# ProProject___2023-11-25.net
KiCad netlist of a schematic drawn in EasyEDA Pro
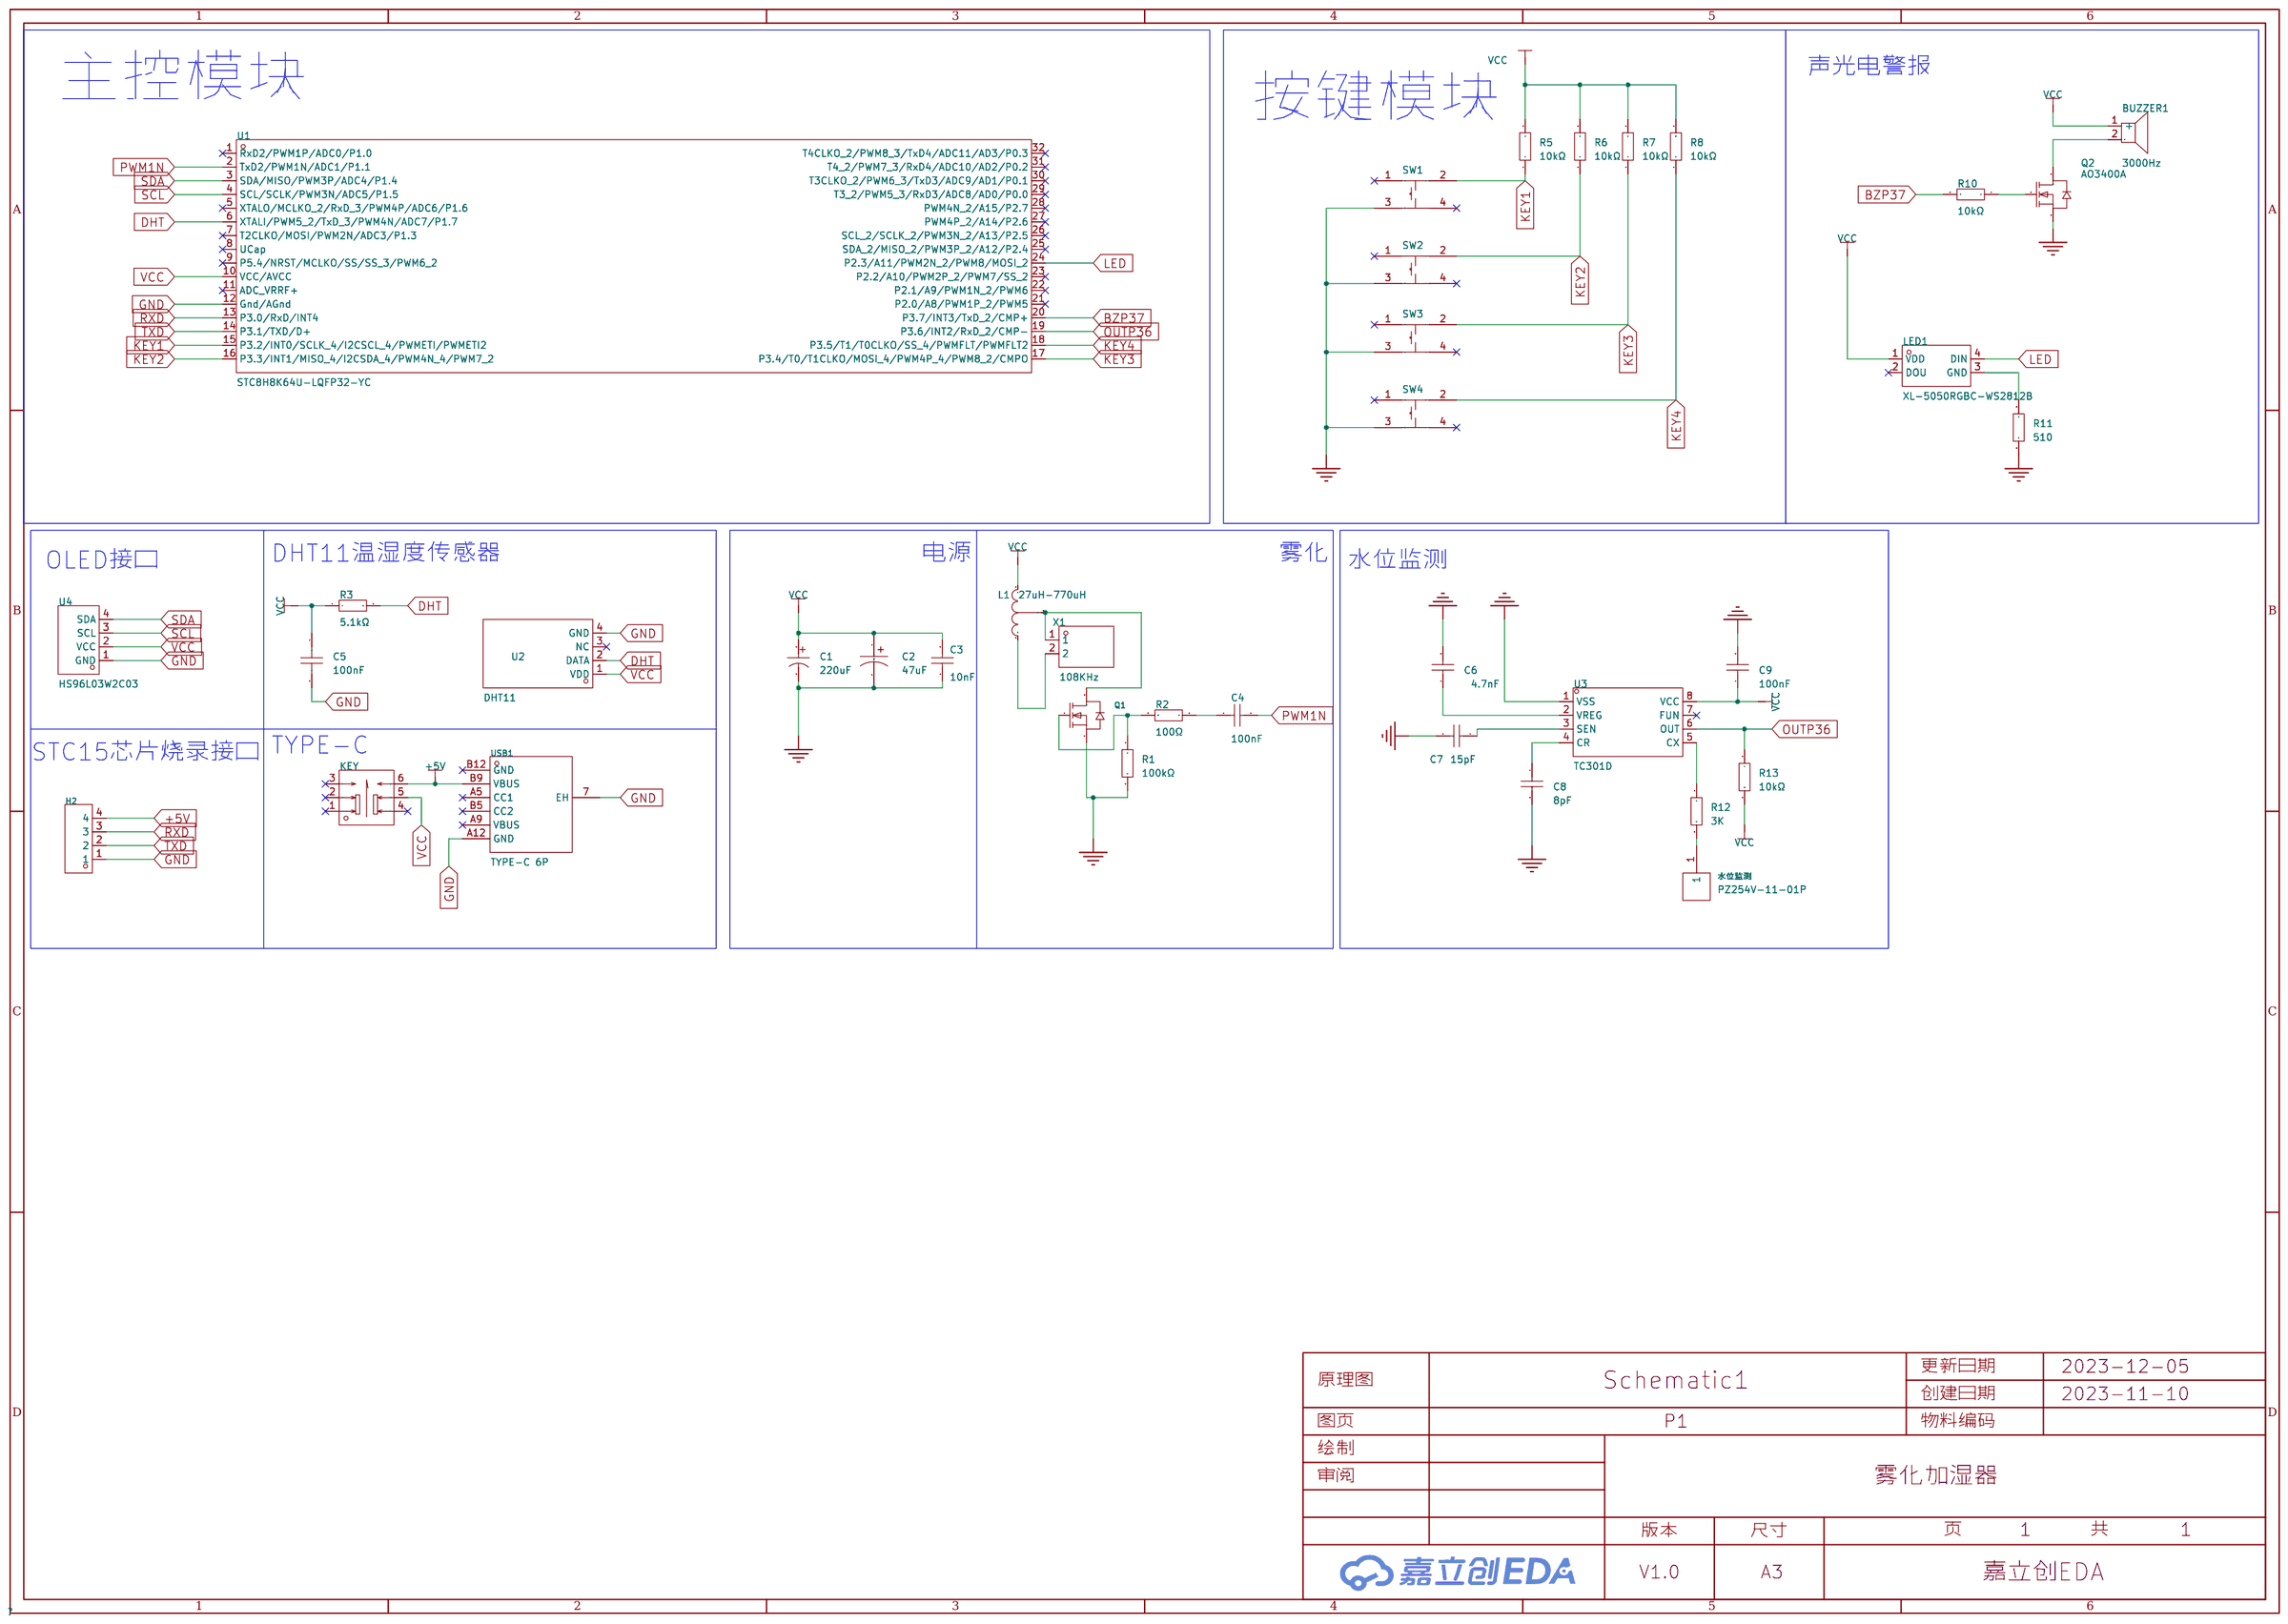
[diagram p0: schematic sheet]

(export (version "E")
  (design (tool "Eeschema 10.0.6"))
  (components
    (comp (ref "BUZZER1")
      (value "3000Hz")
      (footprint "easyedapro:BUZ-TH_BD9.6-P5.00-D0.7-FD")
      (description "驱动方式:有源(内含驱动线路);构造类型:电磁式;额定电压:5V;工作电压:4V~8V;频率:3000Hz;声压(SPL):85dB@5V,10cm;直径(φD):9mm;高度:5.7mm;")
      (fields (field (name "Manufacturer Part") "HNB09A05") (field (name "Manufacturer") "华能"))
      (libsource (lib "easyedapro") (part "HNB09A05"))
    )
    (comp (ref "C1")
      (value "220uF")
      (footprint "easyedapro:CAP-TH_BD10.0-P5.00-D1.0-FD")
      (description "容值:220uF;精度:±20%;额定电压:25V;纹波电流:-;等效串联电阻:-;")
      (fields (field (name "Manufacturer Part") "RNG221M1EBK-1012") (field (name "Manufacturer") "lelon(立隆)"))
      (libsource (lib "easyedapro") (part "RNG221M1EBK-1012"))
    )
    (comp (ref "C2")
      (value "47uF")
      (footprint "easyedapro:CAP-TH_BD5.0-P2.00-D0.8-FD")
      (description "容值:47uF;精度:±20%;额定电压:16V;纹波电流:95mA@100kHz;等效串联电阻:2.5Ω@100kHz;")
      (fields
        (field (name "Manufacturer Part") "01EC1882SHG47uF16V")
        (field (name "Manufacturer") "KNSCHA(科尼盛)")
      )
      (libsource (lib "easyedapro") (part "01EC1882SHG47UF16V"))
    )
    (comp (ref "C3")
      (value "10nF")
      (footprint "easyedapro:C0805")
      (description "容值:10nF;精度:±10%;额定电压:50V;材质(温度系数):X7R;")
      (fields (field (name "Manufacturer Part") "0805B103K500NT") (field (name "Manufacturer") "FH(风华)"))
      (libsource (lib "easyedapro") (part "0805B103K500NT"))
    )
    (comp (ref "C4")
      (value "100nF")
      (footprint "easyedapro:C0805")
      (description "容值:10nF;精度:±10%;额定电压:50V;材质(温度系数):X7R;")
      (fields (field (name "Manufacturer Part") "0805B103K500NT") (field (name "Manufacturer") "FH(风华)"))
      (libsource (lib "easyedapro") (part "0805B103K500NT"))
    )
    (comp (ref "C5")
      (value "100nF")
      (footprint "easyedapro:C0805")
      (description "容值:100nF;精度:±10%;额定电压:50V;材质(温度系数):2X1;")
      (fields
        (field (name "Manufacturer Part") "CT41G-0805-2X1-50V-0.1μF-K(N)")
        (field (name "Manufacturer") "TORCH(火炬)")
      )
      (libsource (lib "easyedapro") (part "CT41G-0805-2X1-50V-0.1UF-K(N)"))
    )
    (comp (ref "C6")
      (value "4.7nF")
      (footprint "easyedapro:C0805")
      (description "容值:10nF;精度:±10%;额定电压:50V;材质(温度系数):X7R;")
      (fields (field (name "Manufacturer Part") "0805B103K500NT") (field (name "Manufacturer") "FH(风华)"))
      (libsource (lib "easyedapro") (part "0805B103K500NT"))
    )
    (comp (ref "C7")
      (value "15pF")
      (footprint "easyedapro:C0805")
      (description "容值:10nF;精度:±10%;额定电压:50V;材质(温度系数):X7R;")
      (fields (field (name "Manufacturer Part") "0805B103K500NT") (field (name "Manufacturer") "FH(风华)"))
      (libsource (lib "easyedapro") (part "0805B103K500NT"))
    )
    (comp (ref "C8")
      (value "8pF")
      (footprint "easyedapro:C0805")
      (description "容值:10nF;精度:±10%;额定电压:50V;材质(温度系数):X7R;")
      (fields (field (name "Manufacturer Part") "0805B103K500NT") (field (name "Manufacturer") "FH(风华)"))
      (libsource (lib "easyedapro") (part "0805B103K500NT"))
    )
    (comp (ref "C9")
      (value "100nF")
      (footprint "easyedapro:C0805")
      (description "容值:10nF;精度:±10%;额定电压:50V;材质(温度系数):X7R;")
      (fields (field (name "Manufacturer Part") "0805B103K500NT") (field (name "Manufacturer") "FH(风华)"))
      (libsource (lib "easyedapro") (part "0805B103K500NT"))
    )
    (comp (ref "H2")
      (value "PZ254R-11-04P")
      (footprint "easyedapro:HDR-TH_4P-P2.54-H-M-W10.4")
      (fields (field (name "Manufacturer") "XFCN(兴飞)"))
      (libsource (lib "easyedapro") (part "PZ254R-11-04P"))
    )
    (comp (ref "KEY")
      (value "XKB5858-Z")
      (footprint "easyedapro:SW-TH_6P-L5.8-W5.8-P2.00-LS4.5-BL")
      (fields (field (name "Manufacturer") "XKB Connectivity(中国星坤)"))
      (libsource (lib "easyedapro") (part "XKB5858-Z"))
    )
    (comp (ref "L1")
      (value "27uH-770uH")
      (footprint "easyedapro:IND-TH_BD9.5-P5.20-D0.6")
      (description "电感值:2.2uH;精度:±20%;额定电流:7A;饱和电流(Isat):11A;")
      (fields (field (name "Manufacturer Part") "PDPTAT0810-2R2M") (field (name "Manufacturer") "PROD(谱罗德)"))
      (libsource (lib "easyedapro") (part "PDPTAT0810-2R2M"))
    )
    (comp (ref "LED1")
      (value "XL-5050RGBC-WS2812B")
      (footprint "easyedapro:LED-SMD_4P-L5.0-W5.0-BL_XL-5050RGBC")
      (description "发光颜色:RGB三色;二极管配置:-;主波长:-;色温:-;功率:-;安装方式:正贴;")
      (fields (field (name "Manufacturer") "XINGLIGHT(成兴光)"))
      (libsource (lib "easyedapro") (part "XL-5050RGBC-WS2812B"))
    )
    (comp (ref "Q1")
      (value "AO3400-HXY")
      (footprint "easyedapro:SOT-23_L2.9-W1.3-P1.90-LS2.4-BR")
      (description "类型:N沟道;漏源电压(Vdss):30V;连续漏极电流(Id):5.8A;功率(Pd):1.4W;导通电阻(RDS(on)@Vgs,Id):28mΩ@10V,5.8A;")
      (fields (field (name "Manufacturer") "HXY MOSFET(华轩阳电子)"))
      (libsource (lib "easyedapro") (part "AO3400_C4748804"))
    )
    (comp (ref "Q2")
      (value "AO3400A")
      (footprint "easyedapro:SOT-23_L2.9-W1.3-P1.90-LS2.4-BR")
      (fields (field (name "Manufacturer") "BORN(伯恩半导体)"))
      (libsource (lib "easyedapro") (part "AO3400A_C344010"))
    )
    (comp (ref "R1")
      (value "100kΩ")
      (footprint "easyedapro:R0805")
      (description "电阻类型:厚膜电阻;阻值:10kΩ;精度:±1%;功率:125mW;")
      (fields
        (field (name "Manufacturer Part") "0805W8F1002T5E")
        (field (name "Manufacturer") "UNI-ROYAL(厚声)")
      )
      (libsource (lib "easyedapro") (part "0805W8F1002T5E"))
    )
    (comp (ref "R2")
      (value "100Ω")
      (footprint "easyedapro:R0805")
      (description "电阻类型:厚膜电阻;阻值:10kΩ;精度:±1%;功率:125mW;")
      (fields
        (field (name "Manufacturer Part") "0805W8F1002T5E")
        (field (name "Manufacturer") "UNI-ROYAL(厚声)")
      )
      (libsource (lib "easyedapro") (part "0805W8F1002T5E"))
    )
    (comp (ref "R3")
      (value "5.1kΩ")
      (footprint "easyedapro:R0805")
      (description "电阻类型:厚膜电阻;阻值:5.1kΩ;精度:±1%;功率:125mW;")
      (fields
        (field (name "Manufacturer Part") "0805W8F5101T5E")
        (field (name "Manufacturer") "UNI-ROYAL(厚声)")
      )
      (libsource (lib "easyedapro") (part "0805W8F5101T5E"))
    )
    (comp (ref "R5")
      (value "10kΩ")
      (footprint "easyedapro:R0805")
      (description "电阻类型:厚膜电阻;阻值:10kΩ;精度:±1%;功率:125mW;")
      (fields
        (field (name "Manufacturer Part") "0805W8F1002T5E")
        (field (name "Manufacturer") "UNI-ROYAL(厚声)")
      )
      (libsource (lib "easyedapro") (part "0805W8F1002T5E"))
    )
    (comp (ref "R6")
      (value "10kΩ")
      (footprint "easyedapro:R0805")
      (description "电阻类型:厚膜电阻;阻值:10kΩ;精度:±1%;功率:125mW;")
      (fields
        (field (name "Manufacturer Part") "0805W8F1002T5E")
        (field (name "Manufacturer") "UNI-ROYAL(厚声)")
      )
      (libsource (lib "easyedapro") (part "0805W8F1002T5E"))
    )
    (comp (ref "R7")
      (value "10kΩ")
      (footprint "easyedapro:R0805")
      (description "电阻类型:厚膜电阻;阻值:10kΩ;精度:±1%;功率:125mW;")
      (fields
        (field (name "Manufacturer Part") "0805W8F1002T5E")
        (field (name "Manufacturer") "UNI-ROYAL(厚声)")
      )
      (libsource (lib "easyedapro") (part "0805W8F1002T5E"))
    )
    (comp (ref "R8")
      (value "10kΩ")
      (footprint "easyedapro:R0805")
      (description "电阻类型:厚膜电阻;阻值:10kΩ;精度:±1%;功率:125mW;")
      (fields
        (field (name "Manufacturer Part") "0805W8F1002T5E")
        (field (name "Manufacturer") "UNI-ROYAL(厚声)")
      )
      (libsource (lib "easyedapro") (part "0805W8F1002T5E"))
    )
    (comp (ref "R10")
      (value "10kΩ")
      (footprint "easyedapro:R0805")
      (description "电阻类型:厚膜电阻;阻值:10kΩ;精度:±1%;功率:125mW;")
      (fields
        (field (name "Manufacturer Part") "0805W8F1002T5E")
        (field (name "Manufacturer") "UNI-ROYAL(厚声)")
      )
      (libsource (lib "easyedapro") (part "0805W8F1002T5E"))
    )
    (comp (ref "R11")
      (value "510")
      (footprint "easyedapro:R0805")
      (description "电阻类型:厚膜电阻;阻值:10kΩ;精度:±1%;功率:125mW;")
      (fields
        (field (name "Manufacturer Part") "0805W8F1002T5E")
        (field (name "Manufacturer") "UNI-ROYAL(厚声)")
      )
      (libsource (lib "easyedapro") (part "0805W8F1002T5E"))
    )
    (comp (ref "R12")
      (value "3K")
      (footprint "easyedapro:R0805")
      (description "电阻类型:厚膜电阻;阻值:10kΩ;精度:±1%;功率:125mW;")
      (fields
        (field (name "Manufacturer Part") "0805W8F1002T5E")
        (field (name "Manufacturer") "UNI-ROYAL(厚声)")
      )
      (libsource (lib "easyedapro") (part "0805W8F1002T5E"))
    )
    (comp (ref "R13")
      (value "10kΩ")
      (footprint "easyedapro:R0805")
      (description "电阻类型:厚膜电阻;阻值:10kΩ;精度:±1%;功率:125mW;")
      (fields
        (field (name "Manufacturer Part") "0805W8F1002T5E")
        (field (name "Manufacturer") "UNI-ROYAL(厚声)")
      )
      (libsource (lib "easyedapro") (part "0805W8F1002T5E"))
    )
    (comp (ref "SW1")
      (value "TS-1009S-03826")
      (footprint "easyedapro:SW-SMD_4P-L4.5-W4.5-P3.00-LS7.0")
      (description "触点电流:50mA;额定电压(DC):12V;电路结构:单刀单掷;安装方式:立贴;带灯:-;机械寿命:-;")
      (fields (field (name "Manufacturer") "XUNPU(讯普)"))
      (libsource (lib "easyedapro") (part "TS-1009S-03826"))
    )
    (comp (ref "SW2")
      (value "TS-1009S-03826")
      (footprint "easyedapro:SW-SMD_4P-L4.5-W4.5-P3.00-LS7.0")
      (description "触点电流:50mA;额定电压(DC):12V;电路结构:单刀单掷;安装方式:立贴;带灯:-;机械寿命:-;")
      (fields (field (name "Manufacturer") "XUNPU(讯普)"))
      (libsource (lib "easyedapro") (part "TS-1009S-03826"))
    )
    (comp (ref "SW3")
      (value "TS-1009S-03826")
      (footprint "easyedapro:SW-SMD_4P-L4.5-W4.5-P3.00-LS7.0")
      (description "触点电流:50mA;额定电压(DC):12V;电路结构:单刀单掷;安装方式:立贴;带灯:-;机械寿命:-;")
      (fields (field (name "Manufacturer") "XUNPU(讯普)"))
      (libsource (lib "easyedapro") (part "TS-1009S-03826"))
    )
    (comp (ref "SW4")
      (value "TS-1009S-03826")
      (footprint "easyedapro:SW-SMD_4P-L4.5-W4.5-P3.00-LS7.0")
      (description "触点电流:50mA;额定电压(DC):12V;电路结构:单刀单掷;安装方式:立贴;带灯:-;机械寿命:-;")
      (fields (field (name "Manufacturer") "XUNPU(讯普)"))
      (libsource (lib "easyedapro") (part "TS-1009S-03826"))
    )
    (comp (ref "U1")
      (value "STC8H8K64U-LQFP32-YC")
      (footprint "easyedapro:LQFP-32_L7.0-W7.0-P0.80-LS9.0-BL")
      (libsource (lib "easyedapro") (part "STC8H8K64U-LQFP32-YC"))
    )
    (comp (ref "U2")
      (value "DHT11")
      (footprint "easyedapro:SENSOR-TH_DHT11")
      (description "新款电容式数字温湿度传感器,老款已停产16.1x12.6x5.8mm")
      (fields (field (name "Manufacturer") "广州奥松"))
      (libsource (lib "easyedapro") (part "DHT11"))
    )
    (comp (ref "U3")
      (value "TC301D")
      (footprint "easyedapro:SO-8_L4.9-W3.9-P1.27-LS5.9-BL")
      (fields (field (name "Manufacturer") "NUTECH(诺泰)"))
      (libsource (lib "easyedapro") (part "TC301D"))
    )
    (comp (ref "U4")
      (value "HS96L03W2C03")
      (footprint "easyedapro:OLED-TH_L27.8-W27.2-P2.54_C9900033791")
      (fields (field (name "Manufacturer") "HS(汉昇)"))
      (libsource (lib "easyedapro") (part "HS96L03W2C03"))
    )
    (comp (ref "USB1")
      (value "TYPE-C 6P")
      (footprint "easyedapro:TYPE-C-SMD_TYPE-C-6P")
      (description "连接器类型:Type-C;标准:-;公母:母座;触点数量:6;端口数量:1;安装方式:卧贴;额定电流 - 电源:-;工作温度范围:-40°C~+85°C;")
      (fields (field (name "Manufacturer") "SHOU HAN(首韩)"))
      (libsource (lib "easyedapro") (part "TYPE-C 6P"))
    )
    (comp (ref "X1")
      (value "108KHz")
      (footprint "easyedapro:CONN-TH_B2B-XH-A-LF-SN")
      (description "参考系列:XH;间距:2.5mm;插针结构:1x2P;排数:1;每排PIN数:2;行距:-;安装方式:-;触头材质:黄铜;")
      (fields (field (name "Manufacturer") "JST"))
      (libsource (lib "easyedapro") (part "B2B-XH-A (LF)(SN)"))
    )
    (comp (ref "水位监测")
      (value "PZ254V-11-01P")
      (footprint "easyedapro:HDR-TH_1P-P2.54-V-M")
      (fields (field (name "Manufacturer") "XFCN(兴飞)"))
      (libsource (lib "easyedapro") (part "PZ254V-11-01P"))
    )
  )
  (nets
    (net (code "1") (name "+5V") (class "Default")
      (node (ref "H2") (pin "4") (pinfunction "4_4") (pintype "input"))
      (node (ref "KEY") (pin "6") (pinfunction "6_6") (pintype "input"))
      (node (ref "USB1") (pin "B9") (pinfunction "VBUS_B9") (pintype "input"))
    )
    (net (code "2") (name "BZP37") (class "Default")
      (node (ref "R10") (pin "2") (pinfunction "2_2") (pintype "input"))
      (node (ref "U1") (pin "20") (pinfunction "P3.7/INT3/TxD_2/CMP+_20") (pintype "input"))
    )
    (net (code "3") (name "DHT") (class "Default")
      (node (ref "R3") (pin "2") (pinfunction "2_2") (pintype "input"))
      (node (ref "U1") (pin "6") (pinfunction "XTALI/PWM5_2/TxD_3/PWM4N/ADC7/P1.7_6") (pintype "input"))
      (node (ref "U2") (pin "2") (pinfunction "DATA_2") (pintype "unspecified"))
    )
    (net (code "4") (name "GND") (class "Default")
      (node (ref "C1") (pin "2") (pinfunction "2_2") (pintype "input"))
      (node (ref "C2") (pin "2") (pinfunction "2_2") (pintype "input"))
      (node (ref "C3") (pin "1") (pinfunction "1_1") (pintype "input"))
      (node (ref "C5") (pin "2") (pinfunction "2_2") (pintype "unspecified"))
      (node (ref "C6") (pin "2") (pinfunction "2_2") (pintype "input"))
      (node (ref "C7") (pin "2") (pinfunction "2_2") (pintype "input"))
      (node (ref "C8") (pin "2") (pinfunction "2_2") (pintype "input"))
      (node (ref "C9") (pin "2") (pinfunction "2_2") (pintype "input"))
      (node (ref "H2") (pin "1") (pinfunction "1_1") (pintype "input"))
      (node (ref "Q1") (pin "2") (pinfunction "S_2") (pintype "input"))
      (node (ref "Q2") (pin "2") (pinfunction "S_2") (pintype "input"))
      (node (ref "R1") (pin "2") (pinfunction "2_2") (pintype "input"))
      (node (ref "R11") (pin "1") (pinfunction "1_1") (pintype "input"))
      (node (ref "SW1") (pin "3") (pinfunction "3_3") (pintype "input"))
      (node (ref "SW2") (pin "3") (pinfunction "3_3") (pintype "input"))
      (node (ref "SW3") (pin "3") (pinfunction "3_3") (pintype "input"))
      (node (ref "SW4") (pin "3") (pinfunction "3_3") (pintype "input"))
      (node (ref "U1") (pin "12") (pinfunction "Gnd/AGnd_12") (pintype "input"))
      (node (ref "U2") (pin "4") (pinfunction "GND_4") (pintype "unspecified"))
      (node (ref "U3") (pin "1") (pinfunction "VSS_1") (pintype "input"))
      (node (ref "U4") (pin "1") (pinfunction "GND_1") (pintype "unspecified"))
      (node (ref "USB1") (pin "7") (pinfunction "EH_7") (pintype "input"))
      (node (ref "USB1") (pin "A12") (pinfunction "GND_A12") (pintype "input"))
    )
    (net (code "5") (name "KEY1") (class "Default")
      (node (ref "R5") (pin "1") (pinfunction "1_1") (pintype "input"))
      (node (ref "SW1") (pin "2") (pinfunction "2_2") (pintype "input"))
      (node (ref "U1") (pin "15") (pinfunction "P3.2/INT0/SCLK_4/I2CSCL_4/PWMETI/PWMETI2_15") (pintype "input"))
    )
    (net (code "6") (name "KEY2") (class "Default")
      (node (ref "R6") (pin "1") (pinfunction "1_1") (pintype "input"))
      (node (ref "SW2") (pin "2") (pinfunction "2_2") (pintype "input"))
      (node (ref "U1") (pin "16") (pinfunction "P3.3/INT1/MISO_4/I2CSDA_4/PWM4N_4/PWM7_2_16") (pintype "input"))
    )
    (net (code "7") (name "KEY3") (class "Default")
      (node (ref "R7") (pin "1") (pinfunction "1_1") (pintype "input"))
      (node (ref "SW3") (pin "2") (pinfunction "2_2") (pintype "input"))
      (node (ref "U1") (pin "17") (pinfunction "P3.4/T0/T1CLKO/MOSI_4/PWM4P_4/PWM8_2/CMPO_17") (pintype "input"))
    )
    (net (code "8") (name "KEY4") (class "Default")
      (node (ref "R8") (pin "1") (pinfunction "1_1") (pintype "input"))
      (node (ref "SW4") (pin "2") (pinfunction "2_2") (pintype "input"))
      (node (ref "U1") (pin "18") (pinfunction "P3.5/T1/T0CLKO/SS_4/PWMFLT/PWMFLT2_18") (pintype "input"))
    )
    (net (code "9") (name "LED") (class "Default")
      (node (ref "LED1") (pin "4") (pinfunction "DIN_4") (pintype "input"))
      (node (ref "U1") (pin "24") (pinfunction "P2.3/A11/PWM2N_2/PWM8/MOSI_2_24") (pintype "input"))
    )
    (net (code "10") (name "Net-(C4-Pad1)") (class "Default")
      (node (ref "C4") (pin "1") (pinfunction "1_1") (pintype "input"))
      (node (ref "R2") (pin "1") (pinfunction "1_1") (pintype "input"))
    )
    (net (code "11") (name "Net-(L1-Pad2)") (class "Default")
      (node (ref "L1") (pin "2") (pinfunction "2_2") (pintype "unspecified"))
      (node (ref "X1") (pin "2") (pinfunction "2_2") (pintype "unspecified"))
    )
    (net (code "12") (name "Net-(LED1-GND)") (class "Default")
      (node (ref "LED1") (pin "3") (pinfunction "GND_3") (pintype "input"))
      (node (ref "R11") (pin "2") (pinfunction "2_2") (pintype "input"))
    )
    (net (code "13") (name "Net-(Q1-D)") (class "Default")
      (node (ref "L1") (pin "3") (pinfunction "3_3") (pintype "unspecified"))
      (node (ref "Q1") (pin "3") (pinfunction "D_3") (pintype "input"))
      (node (ref "X1") (pin "1") (pinfunction "1_1") (pintype "unspecified"))
    )
    (net (code "14") (name "Net-(Q1-G)") (class "Default")
      (node (ref "Q1") (pin "1") (pinfunction "G_1") (pintype "input"))
      (node (ref "R1") (pin "1") (pinfunction "1_1") (pintype "input"))
      (node (ref "R2") (pin "2") (pinfunction "2_2") (pintype "input"))
    )
    (net (code "15") (name "Net-(Q2-D)") (class "Default")
      (node (ref "BUZZER1") (pin "2") (pinfunction "2_2") (pintype "input"))
      (node (ref "Q2") (pin "3") (pinfunction "D_3") (pintype "input"))
    )
    (net (code "16") (name "Net-(Q2-G)") (class "Default")
      (node (ref "Q2") (pin "1") (pinfunction "G_1") (pintype "input"))
      (node (ref "R10") (pin "1") (pinfunction "1_1") (pintype "input"))
    )
    (net (code "17") (name "Net-(R12-Pad2)") (class "Default")
      (node (ref "R12") (pin "2") (pinfunction "2_2") (pintype "input"))
      (node (ref "水位监测") (pin "1") (pinfunction "1_1") (pintype "input"))
    )
    (net (code "18") (name "Net-(U3-CR)") (class "Default")
      (node (ref "C8") (pin "1") (pinfunction "1_1") (pintype "input"))
      (node (ref "U3") (pin "4") (pinfunction "CR_4") (pintype "input"))
    )
    (net (code "19") (name "Net-(U3-CX)") (class "Default")
      (node (ref "R12") (pin "1") (pinfunction "1_1") (pintype "input"))
      (node (ref "U3") (pin "5") (pinfunction "CX_5") (pintype "input"))
    )
    (net (code "20") (name "Net-(U3-SEN)") (class "Default")
      (node (ref "C7") (pin "1") (pinfunction "1_1") (pintype "input"))
      (node (ref "U3") (pin "3") (pinfunction "SEN_3") (pintype "input"))
    )
    (net (code "21") (name "Net-(U3-VREG)") (class "Default")
      (node (ref "C6") (pin "1") (pinfunction "1_1") (pintype "input"))
      (node (ref "U3") (pin "2") (pinfunction "VREG_2") (pintype "input"))
    )
    (net (code "22") (name "OUTP36") (class "Default")
      (node (ref "R13") (pin "1") (pinfunction "1_1") (pintype "input"))
      (node (ref "U1") (pin "19") (pinfunction "P3.6/INT2/RxD_2/CMP-_19") (pintype "input"))
      (node (ref "U3") (pin "6") (pinfunction "OUT_6") (pintype "input"))
    )
    (net (code "23") (name "PWM1N") (class "Default")
      (node (ref "C4") (pin "2") (pinfunction "2_2") (pintype "input"))
      (node (ref "U1") (pin "2") (pinfunction "TxD2/PWM1N/ADC1/P1.1_2") (pintype "input"))
    )
    (net (code "24") (name "RXD") (class "Default")
      (node (ref "H2") (pin "3") (pinfunction "3_3") (pintype "input"))
      (node (ref "U1") (pin "13") (pinfunction "P3.0/RxD/INT4_13") (pintype "input"))
    )
    (net (code "25") (name "SCL") (class "Default")
      (node (ref "U1") (pin "4") (pinfunction "SCL/SCLK/PWM3N/ADC5/P1.5_4") (pintype "input"))
      (node (ref "U4") (pin "3") (pinfunction "SCL_3") (pintype "unspecified"))
    )
    (net (code "26") (name "SDA") (class "Default")
      (node (ref "U1") (pin "3") (pinfunction "SDA/MISO/PWM3P/ADC4/P1.4_3") (pintype "input"))
      (node (ref "U4") (pin "4") (pinfunction "SDA_4") (pintype "unspecified"))
    )
    (net (code "27") (name "TXD") (class "Default")
      (node (ref "H2") (pin "2") (pinfunction "2_2") (pintype "input"))
      (node (ref "U1") (pin "14") (pinfunction "P3.1/TXD/D+_14") (pintype "input"))
    )
    (net (code "28") (name "VCC") (class "Default")
      (node (ref "BUZZER1") (pin "1") (pinfunction "+_1") (pintype "input"))
      (node (ref "C1") (pin "1") (pinfunction "1_1") (pintype "input"))
      (node (ref "C2") (pin "1") (pinfunction "1_1") (pintype "input"))
      (node (ref "C3") (pin "2") (pinfunction "2_2") (pintype "input"))
      (node (ref "C5") (pin "1") (pinfunction "1_1") (pintype "unspecified"))
      (node (ref "C9") (pin "1") (pinfunction "1_1") (pintype "input"))
      (node (ref "KEY") (pin "5") (pinfunction "5_5") (pintype "input"))
      (node (ref "L1") (pin "1") (pinfunction "1_1") (pintype "unspecified"))
      (node (ref "LED1") (pin "1") (pinfunction "VDD_1") (pintype "input"))
      (node (ref "R13") (pin "2") (pinfunction "2_2") (pintype "input"))
      (node (ref "R3") (pin "1") (pinfunction "1_1") (pintype "input"))
      (node (ref "R5") (pin "2") (pinfunction "2_2") (pintype "input"))
      (node (ref "R6") (pin "2") (pinfunction "2_2") (pintype "input"))
      (node (ref "R7") (pin "2") (pinfunction "2_2") (pintype "input"))
      (node (ref "R8") (pin "2") (pinfunction "2_2") (pintype "input"))
      (node (ref "U1") (pin "10") (pinfunction "VCC/AVCC_10") (pintype "input"))
      (node (ref "U2") (pin "1") (pinfunction "VDD_1") (pintype "unspecified"))
      (node (ref "U3") (pin "8") (pinfunction "VCC_8") (pintype "input"))
      (node (ref "U4") (pin "2") (pinfunction "VCC_2") (pintype "unspecified"))
    )
    (net (code "29") (name "unconnected-(KEY-Pad1)") (class "Default")
      (node (ref "KEY") (pin "1") (pinfunction "1_1") (pintype "input+no_connect"))
    )
    (net (code "30") (name "unconnected-(KEY-Pad2)") (class "Default")
      (node (ref "KEY") (pin "2") (pinfunction "2_2") (pintype "input+no_connect"))
    )
    (net (code "31") (name "unconnected-(KEY-Pad3)") (class "Default")
      (node (ref "KEY") (pin "3") (pinfunction "3_3") (pintype "input+no_connect"))
    )
    (net (code "32") (name "unconnected-(KEY-Pad4)") (class "Default")
      (node (ref "KEY") (pin "4") (pinfunction "4_4") (pintype "input+no_connect"))
    )
    (net (code "33") (name "unconnected-(LED1-DOU-Pad2)") (class "Default")
      (node (ref "LED1") (pin "2") (pinfunction "DOU_2") (pintype "input+no_connect"))
    )
    (net (code "34") (name "unconnected-(SW1-Pad1)") (class "Default")
      (node (ref "SW1") (pin "1") (pinfunction "1_1") (pintype "input+no_connect"))
    )
    (net (code "35") (name "unconnected-(SW1-Pad4)") (class "Default")
      (node (ref "SW1") (pin "4") (pinfunction "4_4") (pintype "input+no_connect"))
    )
    (net (code "36") (name "unconnected-(SW2-Pad1)") (class "Default")
      (node (ref "SW2") (pin "1") (pinfunction "1_1") (pintype "input+no_connect"))
    )
    (net (code "37") (name "unconnected-(SW2-Pad4)") (class "Default")
      (node (ref "SW2") (pin "4") (pinfunction "4_4") (pintype "input+no_connect"))
    )
    (net (code "38") (name "unconnected-(SW3-Pad1)") (class "Default")
      (node (ref "SW3") (pin "1") (pinfunction "1_1") (pintype "input+no_connect"))
    )
    (net (code "39") (name "unconnected-(SW3-Pad4)") (class "Default")
      (node (ref "SW3") (pin "4") (pinfunction "4_4") (pintype "input+no_connect"))
    )
    (net (code "40") (name "unconnected-(SW4-Pad1)") (class "Default")
      (node (ref "SW4") (pin "1") (pinfunction "1_1") (pintype "input+no_connect"))
    )
    (net (code "41") (name "unconnected-(SW4-Pad4)") (class "Default")
      (node (ref "SW4") (pin "4") (pinfunction "4_4") (pintype "input+no_connect"))
    )
    (net (code "42") (name "unconnected-(U1-ADC_VRRF+-Pad11)") (class "Default")
      (node (ref "U1") (pin "11") (pinfunction "ADC_VRRF+_11") (pintype "input+no_connect"))
    )
    (net (code "43") (name "unconnected-(U1-P2.0{slash}A8{slash}PWM1P_2{slash}PWM5-Pad21)") (class "Default")
      (node (ref "U1") (pin "21") (pinfunction "P2.0/A8/PWM1P_2/PWM5_21") (pintype "input+no_connect"))
    )
    (net (code "44") (name "unconnected-(U1-P2.1{slash}A9{slash}PWM1N_2{slash}PWM6-Pad22)") (class "Default")
      (node (ref "U1") (pin "22") (pinfunction "P2.1/A9/PWM1N_2/PWM6_22") (pintype "input+no_connect"))
    )
    (net (code "45") (name "unconnected-(U1-P2.2{slash}A10{slash}PWM2P_2{slash}PWM7{slash}SS_2-Pad23)") (class "Default")
      (node (ref "U1") (pin "23") (pinfunction "P2.2/A10/PWM2P_2/PWM7/SS_2_23") (pintype "input+no_connect"))
    )
    (net (code "46") (name "unconnected-(U1-P5.4{slash}NRST{slash}MCLKO{slash}SS{slash}SS_3{slash}PWM6_2-Pad9)") (class "Default")
      (node (ref "U1") (pin "9") (pinfunction "P5.4/NRST/MCLKO/SS/SS_3/PWM6_2_9") (pintype "input+no_connect"))
    )
    (net (code "47") (name "unconnected-(U1-PWM4N_2{slash}A15{slash}P2.7-Pad28)") (class "Default")
      (node (ref "U1") (pin "28") (pinfunction "PWM4N_2/A15/P2.7_28") (pintype "input+no_connect"))
    )
    (net (code "48") (name "unconnected-(U1-PWM4P_2{slash}A14{slash}P2.6-Pad27)") (class "Default")
      (node (ref "U1") (pin "27") (pinfunction "PWM4P_2/A14/P2.6_27") (pintype "input+no_connect"))
    )
    (net (code "49") (name "unconnected-(U1-RxD2{slash}PWM1P{slash}ADC0{slash}P1.0-Pad1)") (class "Default")
      (node (ref "U1") (pin "1") (pinfunction "RxD2/PWM1P/ADC0/P1.0_1") (pintype "input+no_connect"))
    )
    (net (code "50") (name "unconnected-(U1-SCL_2{slash}SCLK_2{slash}PWM3N_2{slash}A13{slash}P2.5-Pad26)") (class "Default")
      (node (ref "U1") (pin "26") (pinfunction "SCL_2/SCLK_2/PWM3N_2/A13/P2.5_26") (pintype "input+no_connect"))
    )
    (net (code "51") (name "unconnected-(U1-SDA_2{slash}MISO_2{slash}PWM3P_2{slash}A12{slash}P2.4-Pad25)") (class "Default")
      (node (ref "U1") (pin "25") (pinfunction "SDA_2/MISO_2/PWM3P_2/A12/P2.4_25") (pintype "input+no_connect"))
    )
    (net (code "52") (name "unconnected-(U1-T2CLKO{slash}MOSI{slash}PWM2N{slash}ADC3{slash}P1.3-Pad7)") (class "Default")
      (node (ref "U1") (pin "7") (pinfunction "T2CLKO/MOSI/PWM2N/ADC3/P1.3_7") (pintype "input+no_connect"))
    )
    (net (code "53") (name "unconnected-(U1-T3CLKO_2{slash}PWM6_3{slash}TxD3{slash}ADC9{slash}AD1{slash}P0.1-Pad30)") (class "Default")
      (node (ref "U1") (pin "30") (pinfunction "T3CLKO_2/PWM6_3/TxD3/ADC9/AD1/P0.1_30") (pintype "input+no_connect"))
    )
    (net (code "54") (name "unconnected-(U1-T3_2{slash}PWM5_3{slash}RxD3{slash}ADC8{slash}AD0{slash}P0.0-Pad29)") (class "Default")
      (node (ref "U1") (pin "29") (pinfunction "T3_2/PWM5_3/RxD3/ADC8/AD0/P0.0_29") (pintype "input+no_connect"))
    )
    (net (code "55") (name "unconnected-(U1-T4CLKO_2{slash}PWM8_3{slash}TxD4{slash}ADC11{slash}AD3{slash}P0.3-Pad32)") (class "Default")
      (node (ref "U1") (pin "32") (pinfunction "T4CLKO_2/PWM8_3/TxD4/ADC11/AD3/P0.3_32") (pintype "input+no_connect"))
    )
    (net (code "56") (name "unconnected-(U1-T4_2{slash}PWM7_3{slash}RxD4{slash}ADC10{slash}AD2{slash}P0.2-Pad31)") (class "Default")
      (node (ref "U1") (pin "31") (pinfunction "T4_2/PWM7_3/RxD4/ADC10/AD2/P0.2_31") (pintype "input+no_connect"))
    )
    (net (code "57") (name "unconnected-(U1-UCap-Pad8)") (class "Default")
      (node (ref "U1") (pin "8") (pinfunction "UCap_8") (pintype "input+no_connect"))
    )
    (net (code "58") (name "unconnected-(U1-XTALO{slash}MCLKO_2{slash}RxD_3{slash}PWM4P{slash}ADC6{slash}P1.6-Pad5)") (class "Default")
      (node (ref "U1") (pin "5") (pinfunction "XTALO/MCLKO_2/RxD_3/PWM4P/ADC6/P1.6_5") (pintype "input+no_connect"))
    )
    (net (code "59") (name "unconnected-(U2-NC-Pad3)") (class "Default")
      (node (ref "U2") (pin "3") (pinfunction "NC_3") (pintype "unspecified+no_connect"))
    )
    (net (code "60") (name "unconnected-(U3-FUN-Pad7)") (class "Default")
      (node (ref "U3") (pin "7") (pinfunction "FUN_7") (pintype "input+no_connect"))
    )
    (net (code "61") (name "unconnected-(USB1-CC1-PadA5)") (class "Default")
      (node (ref "USB1") (pin "A5") (pinfunction "CC1_A5") (pintype "input+no_connect"))
    )
    (net (code "62") (name "unconnected-(USB1-CC2-PadB5)") (class "Default")
      (node (ref "USB1") (pin "B5") (pinfunction "CC2_B5") (pintype "input+no_connect"))
    )
    (net (code "63") (name "unconnected-(USB1-GND-PadB12)") (class "Default")
      (node (ref "USB1") (pin "B12") (pinfunction "GND_B12") (pintype "input+no_connect"))
    )
    (net (code "64") (name "unconnected-(USB1-VBUS-PadA9)") (class "Default")
      (node (ref "USB1") (pin "A9") (pinfunction "VBUS_A9") (pintype "input+no_connect"))
    )
  )
)
